# fpga-bank8-inside.net
KiCad netlist of a schematic drawn in Altium Designer
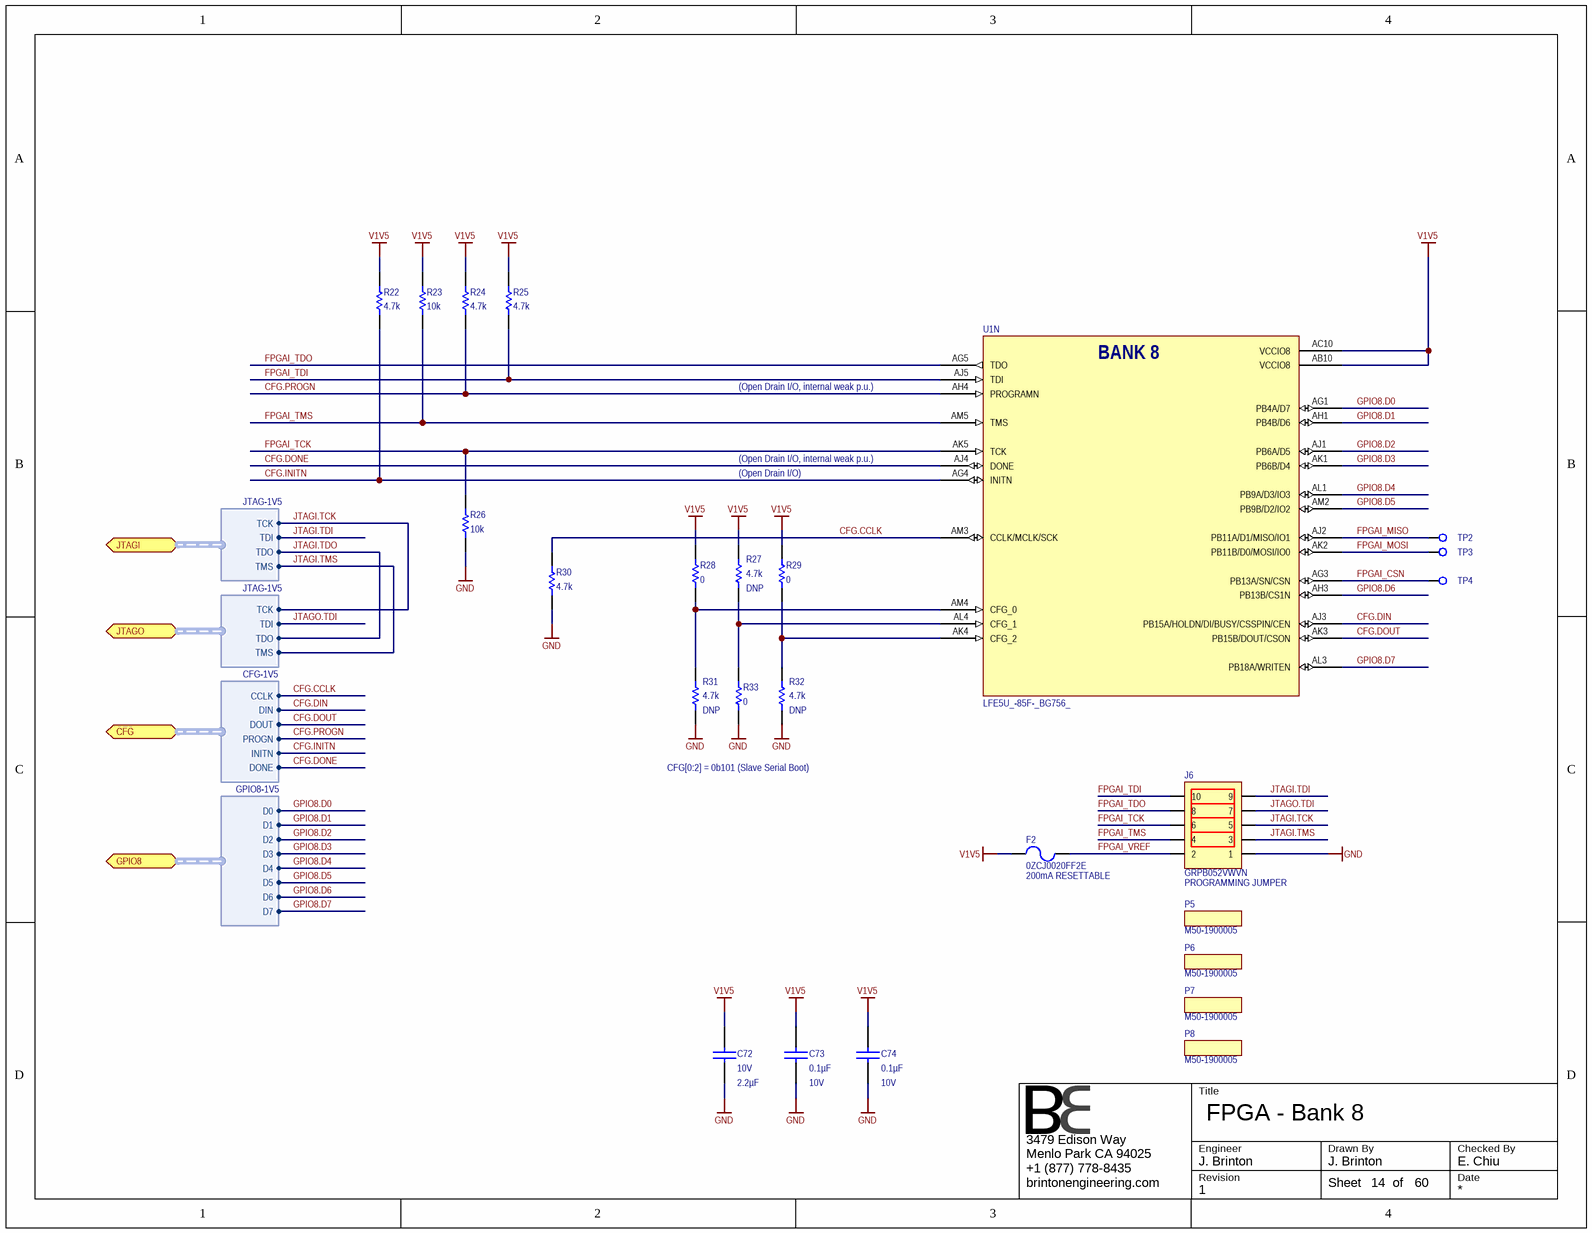
[diagram p0: fpga-bank8-inside.SchDoc]

(export (version "E")
  (design (tool "Eeschema 10.0.6"))
  (components
    (comp (ref "C72")
      (value "GRM188R71A225KE15D")
      (footprint "CAPC1608X90N")
      (description "CAP CER 2.2UF 10V 10% X7R 0603")
      (fields
        (field (name "MANUFACTURER") "Murata Electronics North America")
        (field (name "TOLERANCE") "±10%")
        (field (name "VOLTAGE - RATED") "10V")
        (field (name "CAPACITANCE") "2.2µF")
      )
      (libsource (lib "murata") (part "GRM188R71A225KE15D"))
    )
    (comp (ref "C73")
      (value "GRM155R71A104KA01J")
      (footprint "CAPC1005X56N")
      (description "CAP CER 0.1UF 10V 10% X7R 0402")
      (fields
        (field (name "MANUFACTURER") "Murata Electronics North America")
        (field (name "TOLERANCE") "±10%")
        (field (name "CAPACITANCE") "0.1µF")
        (field (name "VOLTAGE - RATED") "10V")
      )
      (libsource (lib "murata") (part "GRM155R71A104KA01J"))
    )
    (comp (ref "C74")
      (value "GRM155R71A104KA01J")
      (footprint "CAPC1005X56N")
      (description "CAP CER 0.1UF 10V 10% X7R 0402")
      (fields
        (field (name "MANUFACTURER") "Murata Electronics North America")
        (field (name "TOLERANCE") "±10%")
        (field (name "CAPACITANCE") "0.1µF")
        (field (name "VOLTAGE - RATED") "10V")
      )
      (libsource (lib "murata") (part "GRM155R71A104KA01J"))
    )
    (comp (ref "F2")
      (value "0ZCJ0020FF2E")
      (footprint "generic:1206")
      (description "PTC Resettable Fuse, 0.2A, 30V, SMD 1206")
      (fields (field (name "MANUFACTURER") "Bell Fuse"))
      (libsource (lib "bel-fuse") (part "0ZCJ0020FF2E"))
    )
    (comp (ref "J6")
      (value "GRPB052VWVN")
      (footprint "sullins:GRPB052VWVN")
      (description "Male Header, 0.050\" Pitch, 2x5 Position")
      (fields (field (name "MANUFACTURER") "Sullins"))
      (libsource (lib "sullins") (part "GRPB052VWVN"))
    )
    (comp (ref "P5")
      (value "M50-1900005")
      (description "1.27mm Jumper Socket")
      (fields (field (name "MANUFACTURER") "Harwin"))
      (libsource (lib "harwin") (part "M50-1900005"))
    )
    (comp (ref "P6")
      (value "M50-1900005")
      (description "1.27mm Jumper Socket")
      (fields (field (name "MANUFACTURER") "Harwin"))
      (libsource (lib "harwin") (part "M50-1900005"))
    )
    (comp (ref "P7")
      (value "M50-1900005")
      (description "1.27mm Jumper Socket")
      (fields (field (name "MANUFACTURER") "Harwin"))
      (libsource (lib "harwin") (part "M50-1900005"))
    )
    (comp (ref "P8")
      (value "M50-1900005")
      (description "1.27mm Jumper Socket")
      (fields (field (name "MANUFACTURER") "Harwin"))
      (libsource (lib "harwin") (part "M50-1900005"))
    )
    (comp (ref "R22")
      (value "4.7k")
      (footprint "0603")
      (description "Thick Film Resistor 4.7k Ohms +/-1% 0.1W 75V SMD 0603")
      (fields (field (name "TOLERANCE") "+/-1%") (field (name "MANUFACTURER") "Panasonic - ECG"))
      (libsource (lib "brinton") (part "RES"))
    )
    (comp (ref "R23")
      (value "10k")
      (footprint "0603")
      (description "Thick Film Resistor 10k Ohms +/-1% 0.1W SMD 0603")
      (fields (field (name "TOLERANCE") "+/-1%") (field (name "MANUFACTURER") "Panasonic - ECG"))
      (libsource (lib "brinton") (part "RES"))
    )
    (comp (ref "R24")
      (value "4.7k")
      (footprint "0603")
      (description "Thick Film Resistor 4.7k Ohms +/-1% 0.1W 75V SMD 0603")
      (fields (field (name "TOLERANCE") "+/-1%") (field (name "MANUFACTURER") "Panasonic - ECG"))
      (libsource (lib "brinton") (part "RES"))
    )
    (comp (ref "R25")
      (value "4.7k")
      (footprint "0603")
      (description "Thick Film Resistor 4.7k Ohms +/-1% 0.1W 75V SMD 0603")
      (fields (field (name "TOLERANCE") "+/-1%") (field (name "MANUFACTURER") "Panasonic - ECG"))
      (libsource (lib "brinton") (part "RES"))
    )
    (comp (ref "R26")
      (value "10k")
      (footprint "0603")
      (description "Thick Film Resistor 10k Ohms +/-1% 0.1W SMD 0603")
      (fields (field (name "TOLERANCE") "+/-1%") (field (name "MANUFACTURER") "Panasonic - ECG"))
      (libsource (lib "brinton") (part "RES"))
    )
    (comp (ref "R27")
      (value "4.7k")
      (footprint "0603")
      (description "Thick Film Resistor 4.7k Ohms +/-1% 0.1W 75V SMD 0603")
      (fields
        (field (name "TOLERANCE") "+/-1%")
        (field (name "MANUFACTURER") "Panasonic - ECG")
        (field (name "DO NOT PLACE") "DNP")
      )
      (libsource (lib "brinton") (part "RES"))
    )
    (comp (ref "R28")
      (value "0")
      (footprint "0603")
      (description "Thick Film Resistor 0 Ohms SMD 0603")
      (fields (field (name "TOLERANCE") "+/-1%") (field (name "MANUFACTURER") "Panasonic - ECG"))
      (libsource (lib "brinton") (part "RES"))
    )
    (comp (ref "R29")
      (value "0")
      (footprint "0603")
      (description "Thick Film Resistor 0 Ohms SMD 0603")
      (fields (field (name "TOLERANCE") "+/-1%") (field (name "MANUFACTURER") "Panasonic - ECG"))
      (libsource (lib "brinton") (part "RES"))
    )
    (comp (ref "R30")
      (value "4.7k")
      (footprint "0603")
      (description "Thick Film Resistor 4.7k Ohms +/-1% 0.1W 75V SMD 0603")
      (fields (field (name "TOLERANCE") "+/-1%") (field (name "MANUFACTURER") "Panasonic - ECG"))
      (libsource (lib "brinton") (part "RES"))
    )
    (comp (ref "R31")
      (value "4.7k")
      (footprint "0603")
      (description "Thick Film Resistor 4.7k Ohms +/-1% 0.1W 75V SMD 0603")
      (fields
        (field (name "TOLERANCE") "+/-1%")
        (field (name "MANUFACTURER") "Panasonic - ECG")
        (field (name "DO NOT PLACE") "DNP")
      )
      (libsource (lib "brinton") (part "RES"))
    )
    (comp (ref "R32")
      (value "4.7k")
      (footprint "0603")
      (description "Thick Film Resistor 4.7k Ohms +/-1% 0.1W 75V SMD 0603")
      (fields
        (field (name "TOLERANCE") "+/-1%")
        (field (name "MANUFACTURER") "Panasonic - ECG")
        (field (name "DO NOT PLACE") "DNP")
      )
      (libsource (lib "brinton") (part "RES"))
    )
    (comp (ref "R33")
      (value "0")
      (footprint "0603")
      (description "Thick Film Resistor 0 Ohms SMD 0603")
      (fields (field (name "TOLERANCE") "+/-1%") (field (name "MANUFACTURER") "Panasonic - ECG"))
      (libsource (lib "brinton") (part "RES"))
    )
    (comp (ref "TP2")
      (value "TEST_POINT_SMD_10")
      (footprint "generic:TEST_POINT_SMD_10")
      (description "Test Point SMD")
      (libsource (lib "generic") (part "TEST_POINT_SMD_10"))
    )
    (comp (ref "TP3")
      (value "TEST_POINT_SMD_10")
      (footprint "generic:TEST_POINT_SMD_10")
      (description "Test Point SMD")
      (libsource (lib "generic") (part "TEST_POINT_SMD_10"))
    )
    (comp (ref "TP4")
      (value "TEST_POINT_SMD_10")
      (footprint "generic:TEST_POINT_SMD_10")
      (description "Test Point SMD")
      (libsource (lib "generic") (part "TEST_POINT_SMD_10"))
    )
    (comp (ref "U1")
      (value "LFE5U_-85F-_BG756_")
      (footprint "lattice:caBGA756")
      (description "ECP5 FPGA, 85k LUT, 756-caBGA")
      (fields (field (name "MANUFACTURER") "Lattice Semiconductor"))
      (libsource (lib "lattice") (part "LFE5U_-85F-_BG756_"))
    )
  )
  (nets
    (net (code "4") (name "/CFG.CCLK") (class "Default")
      (node (ref "R30") (pin "2") (pinfunction "2_2") (pintype "passive"))
      (node (ref "U1") (pin "AM3") (pinfunction "CCLK/MCLK/SCK_AM3") (pintype "bidirectional"))
    )
    (net (code "5") (name "/CFG.DIN") (class "Default")
      (node (ref "U1") (pin "AJ3") (pinfunction "PB15A/HOLDN/DI/BUSY/CSSPIN/CEN_AJ3") (pintype "bidirectional"))
    )
    (net (code "6") (name "/CFG.DONE") (class "Default")
      (node (ref "U1") (pin "AJ4") (pinfunction "DONE_AJ4") (pintype "bidirectional"))
    )
    (net (code "7") (name "/CFG.DOUT") (class "Default")
      (node (ref "U1") (pin "AK3") (pinfunction "PB15B/DOUT/CSON_AK3") (pintype "bidirectional"))
    )
    (net (code "8") (name "/CFG.INITN") (class "Default")
      (node (ref "R22") (pin "1") (pinfunction "1_1") (pintype "passive"))
      (node (ref "U1") (pin "AG4") (pinfunction "INITN_AG4") (pintype "bidirectional"))
    )
    (net (code "9") (name "/CFG.PROGN") (class "Default")
      (node (ref "R24") (pin "1") (pinfunction "1_1") (pintype "passive"))
      (node (ref "U1") (pin "AH4") (pinfunction "PROGRAMN_AH4") (pintype "input"))
    )
    (net (code "10") (name "/FPGAI_CSN") (class "Default")
      (node (ref "TP4") (pin "1") (pinfunction "1_1") (pintype "passive"))
      (node (ref "U1") (pin "AG3") (pinfunction "PB13A/SN/CSN_AG3") (pintype "bidirectional"))
    )
    (net (code "11") (name "/FPGAI_MISO") (class "Default")
      (node (ref "TP2") (pin "1") (pinfunction "1_1") (pintype "passive"))
      (node (ref "U1") (pin "AJ2") (pinfunction "PB11A/D1/MISO/IO1_AJ2") (pintype "bidirectional"))
    )
    (net (code "12") (name "/FPGAI_MOSI") (class "Default")
      (node (ref "TP3") (pin "1") (pinfunction "1_1") (pintype "passive"))
      (node (ref "U1") (pin "AK2") (pinfunction "PB11B/D0/MOSI/IO0_AK2") (pintype "bidirectional"))
    )
    (net (code "13") (name "/FPGAI_TCK") (class "Default")
      (node (ref "J6") (pin "6") (pinfunction "6_6") (pintype "passive"))
      (node (ref "R26") (pin "2") (pinfunction "2_2") (pintype "passive"))
      (node (ref "U1") (pin "AK5") (pinfunction "TCK_AK5") (pintype "input"))
    )
    (net (code "14") (name "/FPGAI_TDI") (class "Default")
      (node (ref "J6") (pin "10") (pinfunction "10_10") (pintype "passive"))
      (node (ref "R25") (pin "1") (pinfunction "1_1") (pintype "passive"))
      (node (ref "U1") (pin "AJ5") (pinfunction "TDI_AJ5") (pintype "input"))
    )
    (net (code "15") (name "/FPGAI_TDO") (class "Default")
      (node (ref "J6") (pin "8") (pinfunction "8_8") (pintype "passive"))
      (node (ref "U1") (pin "AG5") (pinfunction "TDO_AG5") (pintype "output"))
    )
    (net (code "16") (name "/FPGAI_TMS") (class "Default")
      (node (ref "J6") (pin "4") (pinfunction "4_4") (pintype "passive"))
      (node (ref "R23") (pin "1") (pinfunction "1_1") (pintype "passive"))
      (node (ref "U1") (pin "AM5") (pinfunction "TMS_AM5") (pintype "input"))
    )
    (net (code "17") (name "/FPGAI_VREF") (class "Default")
      (node (ref "F2") (pin "2") (pinfunction "2_2") (pintype "passive"))
      (node (ref "J6") (pin "2") (pinfunction "2_2") (pintype "passive"))
    )
    (net (code "18") (name "/GPIO8.D0") (class "Default")
      (node (ref "U1") (pin "AG1") (pinfunction "PB4A/D7_AG1") (pintype "bidirectional"))
    )
    (net (code "19") (name "/GPIO8.D1") (class "Default")
      (node (ref "U1") (pin "AH1") (pinfunction "PB4B/D6_AH1") (pintype "bidirectional"))
    )
    (net (code "20") (name "/GPIO8.D2") (class "Default")
      (node (ref "U1") (pin "AJ1") (pinfunction "PB6A/D5_AJ1") (pintype "bidirectional"))
    )
    (net (code "21") (name "/GPIO8.D3") (class "Default")
      (node (ref "U1") (pin "AK1") (pinfunction "PB6B/D4_AK1") (pintype "bidirectional"))
    )
    (net (code "22") (name "/GPIO8.D4") (class "Default")
      (node (ref "U1") (pin "AL1") (pinfunction "PB9A/D3/IO3_AL1") (pintype "bidirectional"))
    )
    (net (code "23") (name "/GPIO8.D5") (class "Default")
      (node (ref "U1") (pin "AM2") (pinfunction "PB9B/D2/IO2_AM2") (pintype "bidirectional"))
    )
    (net (code "24") (name "/GPIO8.D6") (class "Default")
      (node (ref "U1") (pin "AH3") (pinfunction "PB13B/CS1N_AH3") (pintype "bidirectional"))
    )
    (net (code "25") (name "/GPIO8.D7") (class "Default")
      (node (ref "U1") (pin "AL3") (pinfunction "PB18A/WRITEN_AL3") (pintype "bidirectional"))
    )
    (net (code "26") (name "/JTAGI.TCK") (class "Default")
      (node (ref "J6") (pin "5") (pinfunction "5_5") (pintype "passive"))
    )
    (net (code "27") (name "/JTAGI.TDI") (class "Default")
      (node (ref "J6") (pin "9") (pinfunction "9_9") (pintype "passive"))
    )
    (net (code "29") (name "/JTAGI.TMS") (class "Default")
      (node (ref "J6") (pin "3") (pinfunction "3_3") (pintype "passive"))
    )
    (net (code "30") (name "/JTAGO.TDI") (class "Default")
      (node (ref "J6") (pin "7") (pinfunction "7_7") (pintype "passive"))
    )
    (net (code "34") (name "GND") (class "Default")
      (node (ref "C72") (pin "1") (pinfunction "1_1") (pintype "passive"))
      (node (ref "C73") (pin "1") (pinfunction "1_1") (pintype "passive"))
      (node (ref "C74") (pin "1") (pinfunction "1_1") (pintype "passive"))
      (node (ref "J6") (pin "1") (pinfunction "1_1") (pintype "passive"))
      (node (ref "R26") (pin "1") (pinfunction "1_1") (pintype "passive"))
      (node (ref "R30") (pin "1") (pinfunction "1_1") (pintype "passive"))
      (node (ref "R31") (pin "1") (pinfunction "1_1") (pintype "passive"))
      (node (ref "R32") (pin "1") (pinfunction "1_1") (pintype "passive"))
      (node (ref "R33") (pin "1") (pinfunction "1_1") (pintype "passive"))
    )
    (net (code "35") (name "Net-(U1N-CFG_0)") (class "Default")
      (node (ref "R28") (pin "1") (pinfunction "1_1") (pintype "passive"))
      (node (ref "R31") (pin "2") (pinfunction "2_2") (pintype "passive"))
      (node (ref "U1") (pin "AM4") (pinfunction "CFG_0_AM4") (pintype "input"))
    )
    (net (code "36") (name "Net-(U1N-CFG_1)") (class "Default")
      (node (ref "R27") (pin "1") (pinfunction "1_1") (pintype "passive"))
      (node (ref "R33") (pin "2") (pinfunction "2_2") (pintype "passive"))
      (node (ref "U1") (pin "AL4") (pinfunction "CFG_1_AL4") (pintype "input"))
    )
    (net (code "37") (name "Net-(U1N-CFG_2)") (class "Default")
      (node (ref "R29") (pin "1") (pinfunction "1_1") (pintype "passive"))
      (node (ref "R32") (pin "2") (pinfunction "2_2") (pintype "passive"))
      (node (ref "U1") (pin "AK4") (pinfunction "CFG_2_AK4") (pintype "input"))
    )
    (net (code "38") (name "V1V5") (class "Default")
      (node (ref "C72") (pin "2") (pinfunction "2_2") (pintype "passive"))
      (node (ref "C73") (pin "2") (pinfunction "2_2") (pintype "passive"))
      (node (ref "C74") (pin "2") (pinfunction "2_2") (pintype "passive"))
      (node (ref "F2") (pin "1") (pinfunction "1_1") (pintype "passive"))
      (node (ref "R22") (pin "2") (pinfunction "2_2") (pintype "passive"))
      (node (ref "R23") (pin "2") (pinfunction "2_2") (pintype "passive"))
      (node (ref "R24") (pin "2") (pinfunction "2_2") (pintype "passive"))
      (node (ref "R25") (pin "2") (pinfunction "2_2") (pintype "passive"))
      (node (ref "R27") (pin "2") (pinfunction "2_2") (pintype "passive"))
      (node (ref "R28") (pin "2") (pinfunction "2_2") (pintype "passive"))
      (node (ref "R29") (pin "2") (pinfunction "2_2") (pintype "passive"))
      (node (ref "U1") (pin "AB10") (pinfunction "VCCIO8_AB10") (pintype "power_in"))
      (node (ref "U1") (pin "AC10") (pinfunction "VCCIO8_AC10") (pintype "power_in"))
    )
  )
)
